# ME433.net
KiCad netlist of a schematic drawn in EAGLE
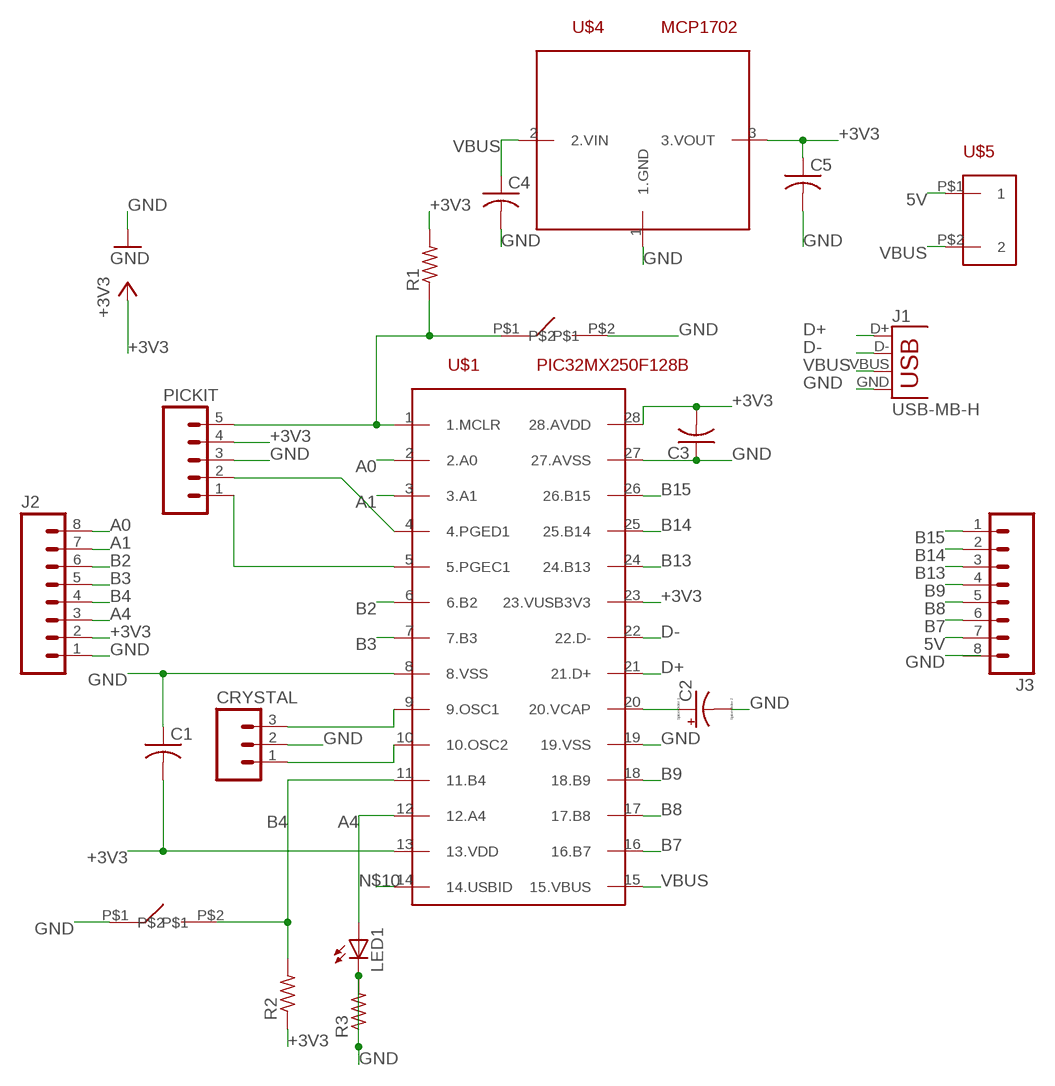
[diagram p0: schematic, sheet 1]

(export (version "E")
  (design (tool "Eeschema 10.0.6"))
  (components
    (comp (ref "C1")
      (value "C-US025-025X050")
      (footprint "eagle-import:C025-025X050")
      (libsource (lib "eagle-import") (part "C-US025-025X050"))
    )
    (comp (ref "C2")
      (value "CPOL-USE2,5-6E")
      (footprint "eagle-import:E2,5-6E")
      (libsource (lib "eagle-import") (part "CPOL-USE2,5-6E"))
    )
    (comp (ref "C3")
      (value "C-US025-025X050")
      (footprint "eagle-import:C025-025X050")
      (libsource (lib "eagle-import") (part "C-US025-025X050"))
    )
    (comp (ref "C4")
      (value "C-US025-025X050")
      (footprint "eagle-import:C025-025X050")
      (libsource (lib "eagle-import") (part "C-US025-025X050"))
    )
    (comp (ref "C5")
      (value "C-US025-025X050")
      (footprint "eagle-import:C025-025X050")
      (libsource (lib "eagle-import") (part "C-US025-025X050"))
    )
    (comp (ref "CRYSTAL")
      (value "M03PTH")
      (footprint "eagle-import:1X03")
      (libsource (lib "eagle-import") (part "M03PTH"))
    )
    (comp (ref "J1")
      (value "USB-MB-H")
      (footprint "eagle-import:USB-MB-H")
      (libsource (lib "eagle-import") (part "USB-MB-H"))
    )
    (comp (ref "J2")
      (value "M08")
      (footprint "eagle-import:1X08_ROUND")
      (libsource (lib "eagle-import") (part "M08"))
    )
    (comp (ref "J3")
      (value "M08")
      (footprint "eagle-import:1X08_ROUND")
      (libsource (lib "eagle-import") (part "M08"))
    )
    (comp (ref "LED1")
      (value "LED3MM")
      (footprint "eagle-import:LED3MM")
      (libsource (lib "eagle-import") (part "LED3MM"))
    )
    (comp (ref "PICKIT")
      (value "M05PTH")
      (footprint "eagle-import:1X05")
      (libsource (lib "eagle-import") (part "M05PTH"))
    )
    (comp (ref "R1")
      (value "R-US_0207/10")
      (footprint "eagle-import:0207_10")
      (libsource (lib "eagle-import") (part "R-US_0207/10"))
    )
    (comp (ref "R2")
      (value "R-US_0207/10")
      (footprint "eagle-import:0207_10")
      (libsource (lib "eagle-import") (part "R-US_0207/10"))
    )
    (comp (ref "R3")
      (value "R-US_0207/10")
      (footprint "eagle-import:0207_10")
      (libsource (lib "eagle-import") (part "R-US_0207/10"))
    )
    (comp (ref "U$1")
      (value "PIC32MX250F128B")
      (footprint "eagle-import:DIL28-3")
      (libsource (lib "eagle-import") (part "PIC32MX250F128B"))
    )
    (comp (ref "U$2")
      (value "PUSHBUTTON")
      (footprint "eagle-import:PUSHBUTTON")
      (libsource (lib "eagle-import") (part "PUSHBUTTON"))
    )
    (comp (ref "U$3")
      (value "PUSHBUTTON")
      (footprint "eagle-import:PUSHBUTTON")
      (libsource (lib "eagle-import") (part "PUSHBUTTON"))
    )
    (comp (ref "U$4")
      (value "MCP1702")
      (footprint "eagle-import:TO92")
      (libsource (lib "eagle-import") (part "MCP1702"))
    )
    (comp (ref "U$5")
      (value "SLIDESWITCH")
      (footprint "eagle-import:SLIDESWITCH")
      (libsource (lib "eagle-import") (part "SLIDESWITCH"))
    )
  )
  (nets
    (net (code "1") (name "+3V3") (class "Default")
      (node (ref "C1") (pin "2") (pinfunction "2_2") (pintype "passive"))
      (node (ref "C3") (pin "2") (pinfunction "2_2") (pintype "passive"))
      (node (ref "C5") (pin "1") (pinfunction "1_1") (pintype "passive"))
      (node (ref "J2") (pin "2") (pinfunction "2_2") (pintype "passive"))
      (node (ref "PICKIT") (pin "4") (pinfunction "4_4") (pintype "passive"))
      (node (ref "R1") (pin "2") (pinfunction "2_2") (pintype "passive"))
      (node (ref "R2") (pin "1") (pinfunction "1_1") (pintype "passive"))
      (node (ref "U$1") (pin "13") (pinfunction "13.VDD_13") (pintype "bidirectional"))
      (node (ref "U$1") (pin "23") (pinfunction "23.VUSB3V3_23") (pintype "bidirectional"))
      (node (ref "U$1") (pin "28") (pinfunction "28.AVDD_28") (pintype "bidirectional"))
      (node (ref "U$4") (pin "3") (pinfunction "3.VOUT_3") (pintype "bidirectional"))
    )
    (net (code "2") (name "/5V") (class "Default")
      (node (ref "J3") (pin "7") (pinfunction "7_7") (pintype "passive"))
      (node (ref "U$5") (pin "P$1") (pinfunction "1_P$1") (pintype "bidirectional"))
    )
    (net (code "3") (name "/A0") (class "Default")
      (node (ref "J2") (pin "8") (pinfunction "8_8") (pintype "passive"))
      (node (ref "U$1") (pin "2") (pinfunction "2.A0_2") (pintype "bidirectional"))
    )
    (net (code "4") (name "/A1") (class "Default")
      (node (ref "J2") (pin "7") (pinfunction "7_7") (pintype "passive"))
      (node (ref "U$1") (pin "3") (pinfunction "3.A1_3") (pintype "bidirectional"))
    )
    (net (code "5") (name "/A4") (class "Default")
      (node (ref "J2") (pin "3") (pinfunction "3_3") (pintype "passive"))
      (node (ref "LED1") (pin "A") (pinfunction "A_A") (pintype "passive"))
      (node (ref "U$1") (pin "12") (pinfunction "12.A4_12") (pintype "bidirectional"))
    )
    (net (code "6") (name "/B2") (class "Default")
      (node (ref "J2") (pin "6") (pinfunction "6_6") (pintype "passive"))
      (node (ref "U$1") (pin "6") (pinfunction "6.B2_6") (pintype "bidirectional"))
    )
    (net (code "7") (name "/B3") (class "Default")
      (node (ref "J2") (pin "5") (pinfunction "5_5") (pintype "passive"))
      (node (ref "U$1") (pin "7") (pinfunction "7.B3_7") (pintype "bidirectional"))
    )
    (net (code "8") (name "/B4") (class "Default")
      (node (ref "J2") (pin "4") (pinfunction "4_4") (pintype "passive"))
      (node (ref "R2") (pin "2") (pinfunction "2_2") (pintype "passive"))
      (node (ref "U$1") (pin "11") (pinfunction "11.B4_11") (pintype "bidirectional"))
      (node (ref "U$3") (pin "P$2") (pinfunction "P$2_P$2") (pintype "bidirectional"))
    )
    (net (code "9") (name "/B7") (class "Default")
      (node (ref "J3") (pin "6") (pinfunction "6_6") (pintype "passive"))
      (node (ref "U$1") (pin "16") (pinfunction "16.B7_16") (pintype "bidirectional"))
    )
    (net (code "10") (name "/B8") (class "Default")
      (node (ref "J3") (pin "5") (pinfunction "5_5") (pintype "passive"))
      (node (ref "U$1") (pin "17") (pinfunction "17.B8_17") (pintype "bidirectional"))
    )
    (net (code "11") (name "/B9") (class "Default")
      (node (ref "J3") (pin "4") (pinfunction "4_4") (pintype "passive"))
      (node (ref "U$1") (pin "18") (pinfunction "18.B9_18") (pintype "bidirectional"))
    )
    (net (code "12") (name "/B13") (class "Default")
      (node (ref "J3") (pin "3") (pinfunction "3_3") (pintype "passive"))
      (node (ref "U$1") (pin "24") (pinfunction "24.B13_24") (pintype "bidirectional"))
    )
    (net (code "13") (name "/B14") (class "Default")
      (node (ref "J3") (pin "2") (pinfunction "2_2") (pintype "passive"))
      (node (ref "U$1") (pin "25") (pinfunction "25.B14_25") (pintype "bidirectional"))
    )
    (net (code "14") (name "/B15") (class "Default")
      (node (ref "J3") (pin "1") (pinfunction "1_1") (pintype "passive"))
      (node (ref "U$1") (pin "26") (pinfunction "26.B15_26") (pintype "bidirectional"))
    )
    (net (code "15") (name "/D+") (class "Default")
      (node (ref "J1") (pin "D+") (pinfunction "D+_D+") (pintype "bidirectional"))
      (node (ref "U$1") (pin "21") (pinfunction "21.D+_21") (pintype "bidirectional"))
    )
    (net (code "16") (name "/D-") (class "Default")
      (node (ref "J1") (pin "D-") (pinfunction "D-_D-") (pintype "bidirectional"))
      (node (ref "U$1") (pin "22") (pinfunction "22.D-_22") (pintype "bidirectional"))
    )
    (net (code "17") (name "/N$10") (class "Default")
      (node (ref "U$1") (pin "14") (pinfunction "14.USBID_14") (pintype "bidirectional"))
    )
    (net (code "18") (name "/VBUS") (class "Default")
      (node (ref "C4") (pin "1") (pinfunction "1_1") (pintype "passive"))
      (node (ref "J1") (pin "VBUS") (pinfunction "VBUS_VBUS") (pintype "bidirectional"))
      (node (ref "U$1") (pin "15") (pinfunction "15.VBUS_15") (pintype "bidirectional"))
      (node (ref "U$4") (pin "2") (pinfunction "2.VIN_2") (pintype "bidirectional"))
      (node (ref "U$5") (pin "P$2") (pinfunction "2_P$2") (pintype "bidirectional"))
    )
    (net (code "19") (name "GND") (class "Default")
      (node (ref "C1") (pin "1") (pinfunction "1_1") (pintype "passive"))
      (node (ref "C2") (pin "+") (pinfunction "+_+") (pintype "passive"))
      (node (ref "C2") (pin "-") (pinfunction "-_-") (pintype "passive"))
      (node (ref "C3") (pin "1") (pinfunction "1_1") (pintype "passive"))
      (node (ref "C4") (pin "2") (pinfunction "2_2") (pintype "passive"))
      (node (ref "C5") (pin "2") (pinfunction "2_2") (pintype "passive"))
      (node (ref "CRYSTAL") (pin "2") (pinfunction "2_2") (pintype "passive"))
      (node (ref "J1") (pin "GND") (pinfunction "GND_GND") (pintype "bidirectional"))
      (node (ref "J2") (pin "1") (pinfunction "1_1") (pintype "passive"))
      (node (ref "LED1") (pin "K") (pinfunction "C_K") (pintype "passive"))
      (node (ref "PICKIT") (pin "3") (pinfunction "3_3") (pintype "passive"))
      (node (ref "R3") (pin "1") (pinfunction "1_1") (pintype "passive"))
      (node (ref "R3") (pin "2") (pinfunction "2_2") (pintype "passive"))
      (node (ref "U$1") (pin "19") (pinfunction "19.VSS_19") (pintype "bidirectional"))
      (node (ref "U$1") (pin "20") (pinfunction "20.VCAP_20") (pintype "bidirectional"))
      (node (ref "U$1") (pin "27") (pinfunction "27.AVSS_27") (pintype "bidirectional"))
      (node (ref "U$1") (pin "8") (pinfunction "8.VSS_8") (pintype "bidirectional"))
      (node (ref "U$2") (pin "P$2") (pinfunction "P$2_P$2") (pintype "bidirectional"))
      (node (ref "U$3") (pin "P$1") (pinfunction "P$1_P$1") (pintype "bidirectional"))
      (node (ref "U$4") (pin "1") (pinfunction "1.GND_1") (pintype "bidirectional"))
    )
    (net (code "20") (name "Net-(U$1-1.MCLR)") (class "Default")
      (node (ref "PICKIT") (pin "5") (pinfunction "5_5") (pintype "passive"))
      (node (ref "R1") (pin "1") (pinfunction "1_1") (pintype "passive"))
      (node (ref "U$1") (pin "1") (pinfunction "1.MCLR_1") (pintype "bidirectional"))
      (node (ref "U$2") (pin "P$1") (pinfunction "P$1_P$1") (pintype "bidirectional"))
    )
    (net (code "21") (name "Net-(U$1-4.PGED1)") (class "Default")
      (node (ref "PICKIT") (pin "2") (pinfunction "2_2") (pintype "passive"))
      (node (ref "U$1") (pin "4") (pinfunction "4.PGED1_4") (pintype "bidirectional"))
    )
    (net (code "22") (name "Net-(U$1-5.PGEC1)") (class "Default")
      (node (ref "PICKIT") (pin "1") (pinfunction "1_1") (pintype "passive"))
      (node (ref "U$1") (pin "5") (pinfunction "5.PGEC1_5") (pintype "bidirectional"))
    )
    (net (code "23") (name "Net-(U$1-9.OSC1)") (class "Default")
      (node (ref "CRYSTAL") (pin "3") (pinfunction "3_3") (pintype "passive"))
      (node (ref "U$1") (pin "9") (pinfunction "9.OSC1_9") (pintype "bidirectional"))
    )
    (net (code "24") (name "Net-(U$1-10.OSC2)") (class "Default")
      (node (ref "CRYSTAL") (pin "1") (pinfunction "1_1") (pintype "passive"))
      (node (ref "U$1") (pin "10") (pinfunction "10.OSC2_10") (pintype "bidirectional"))
    )
    (net (code "25") (name "unconnected-(J3-Pad8)") (class "Default")
      (node (ref "J3") (pin "8") (pinfunction "8_8") (pintype "passive"))
    )
  )
)
